# MAX_BUS.net
KiCad netlist of a schematic drawn in Altium Designer
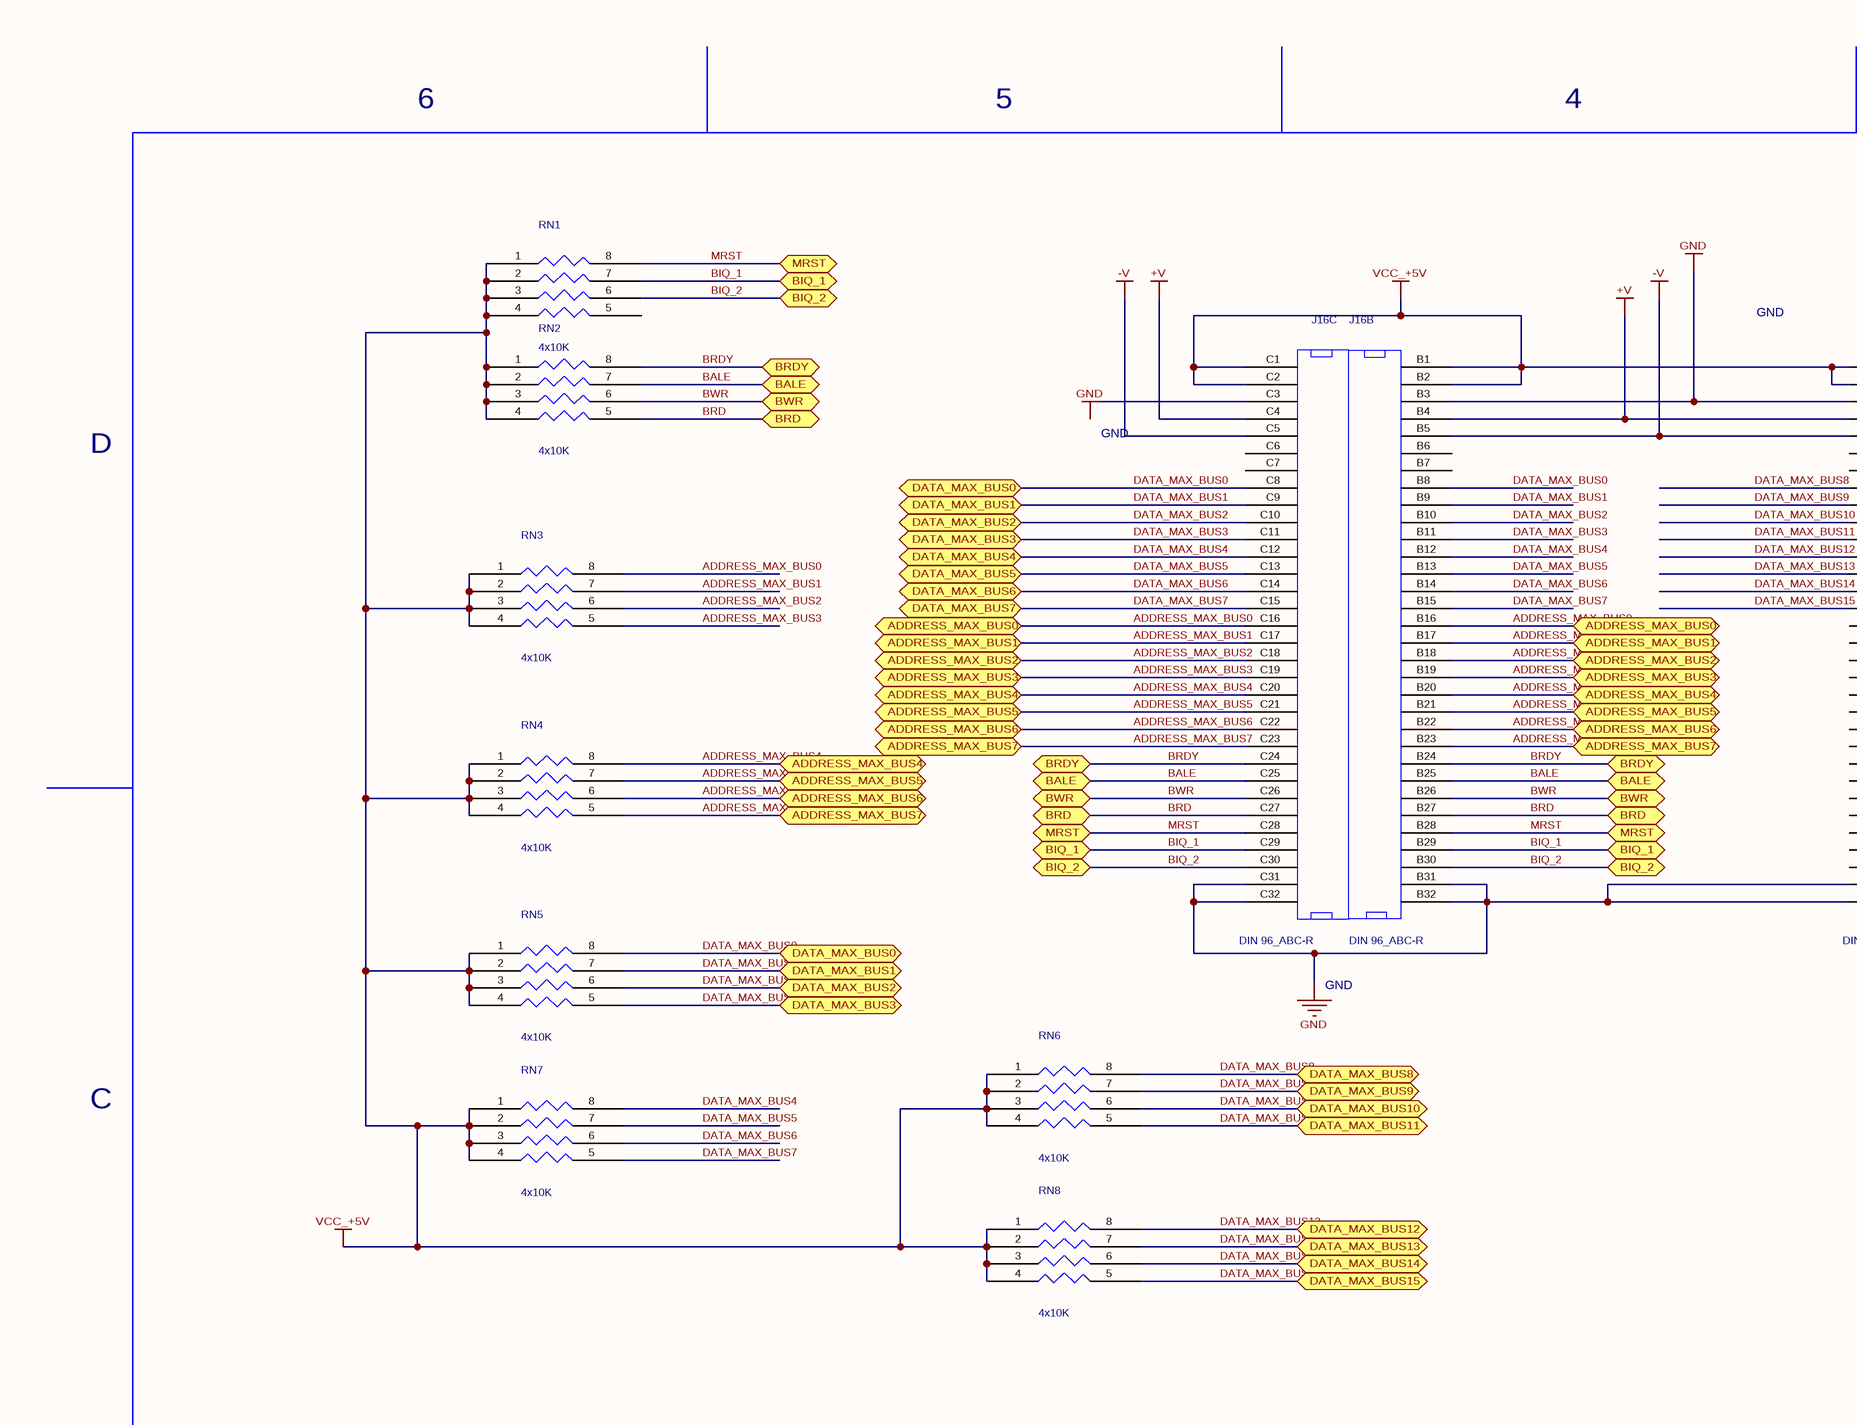
[diagram p0: MAX_BUS.SchDoc, top left]
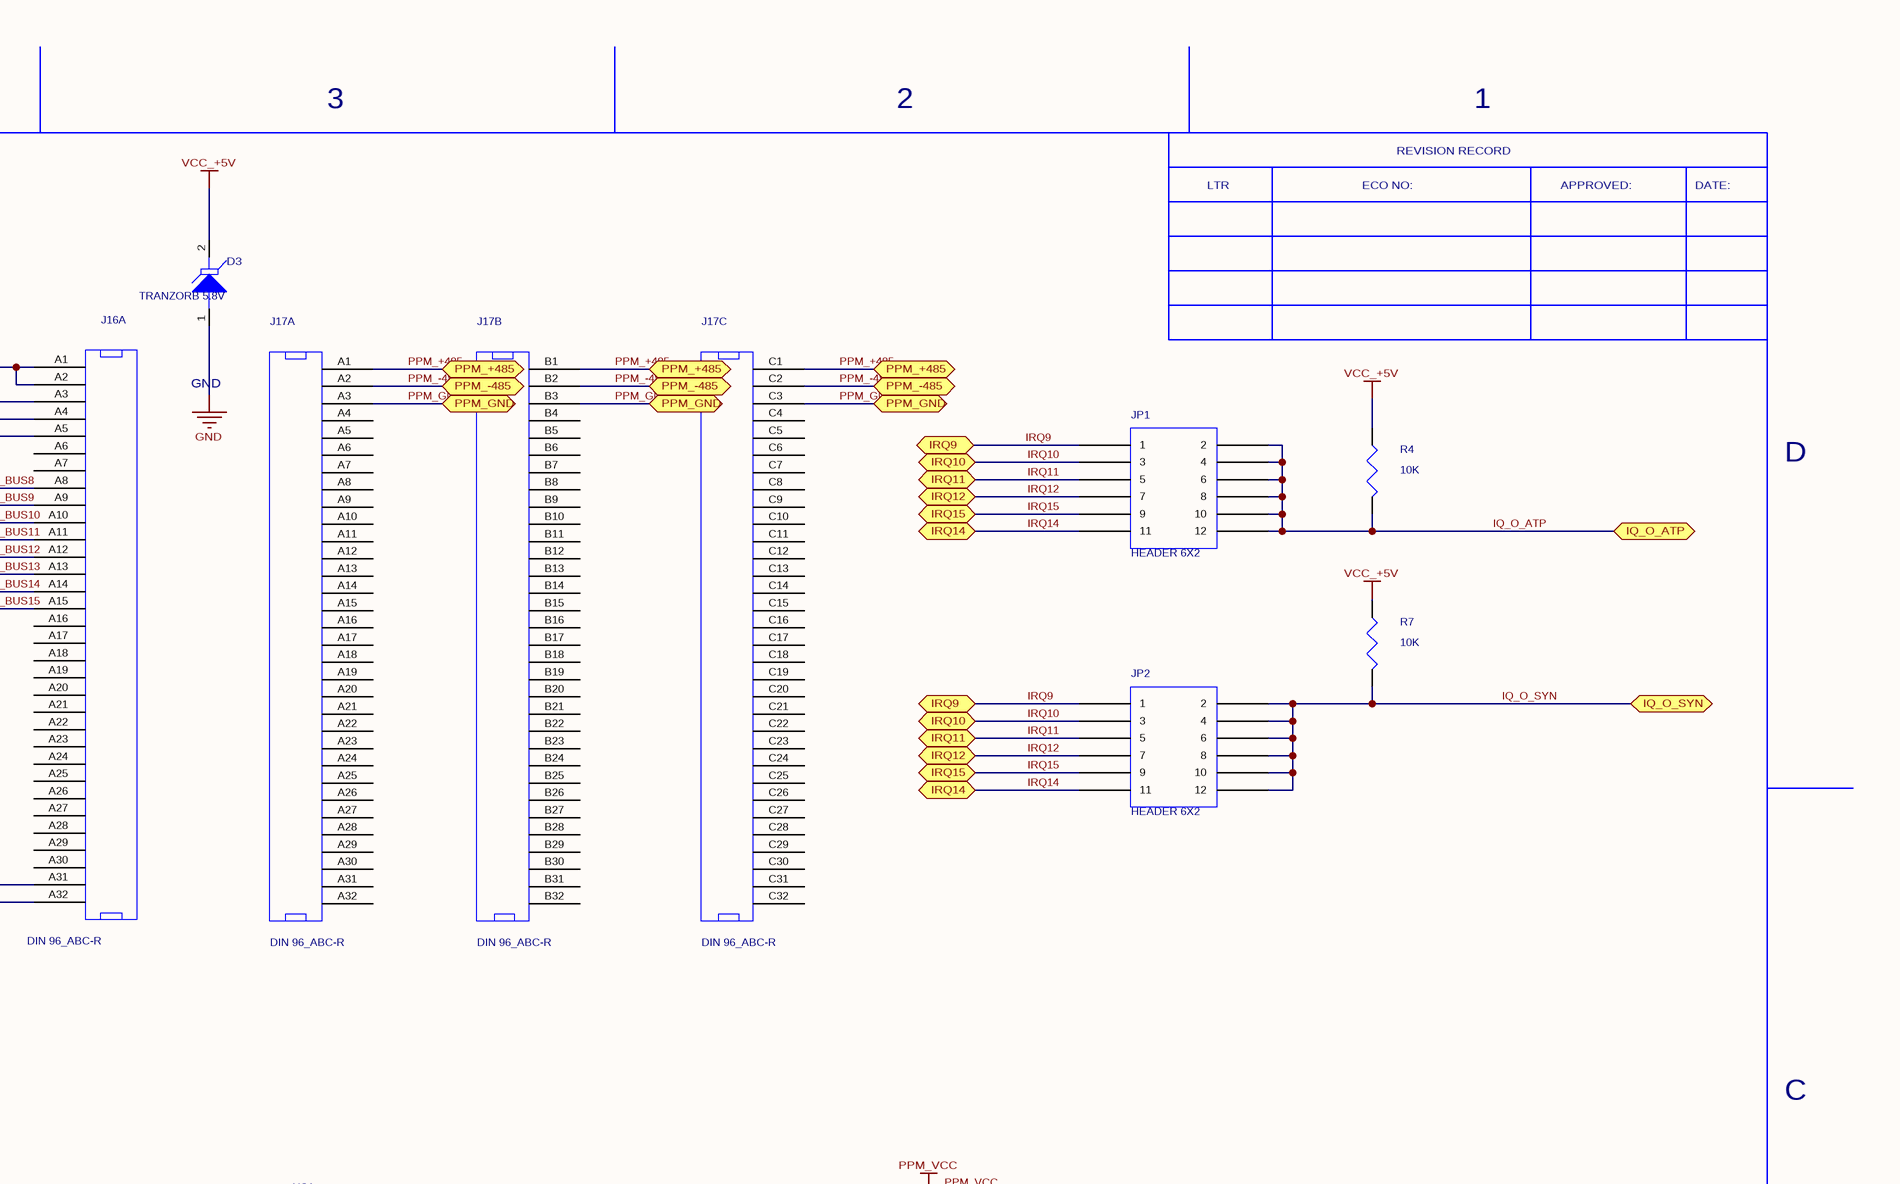
[diagram p1: MAX_BUS.SchDoc, top right]
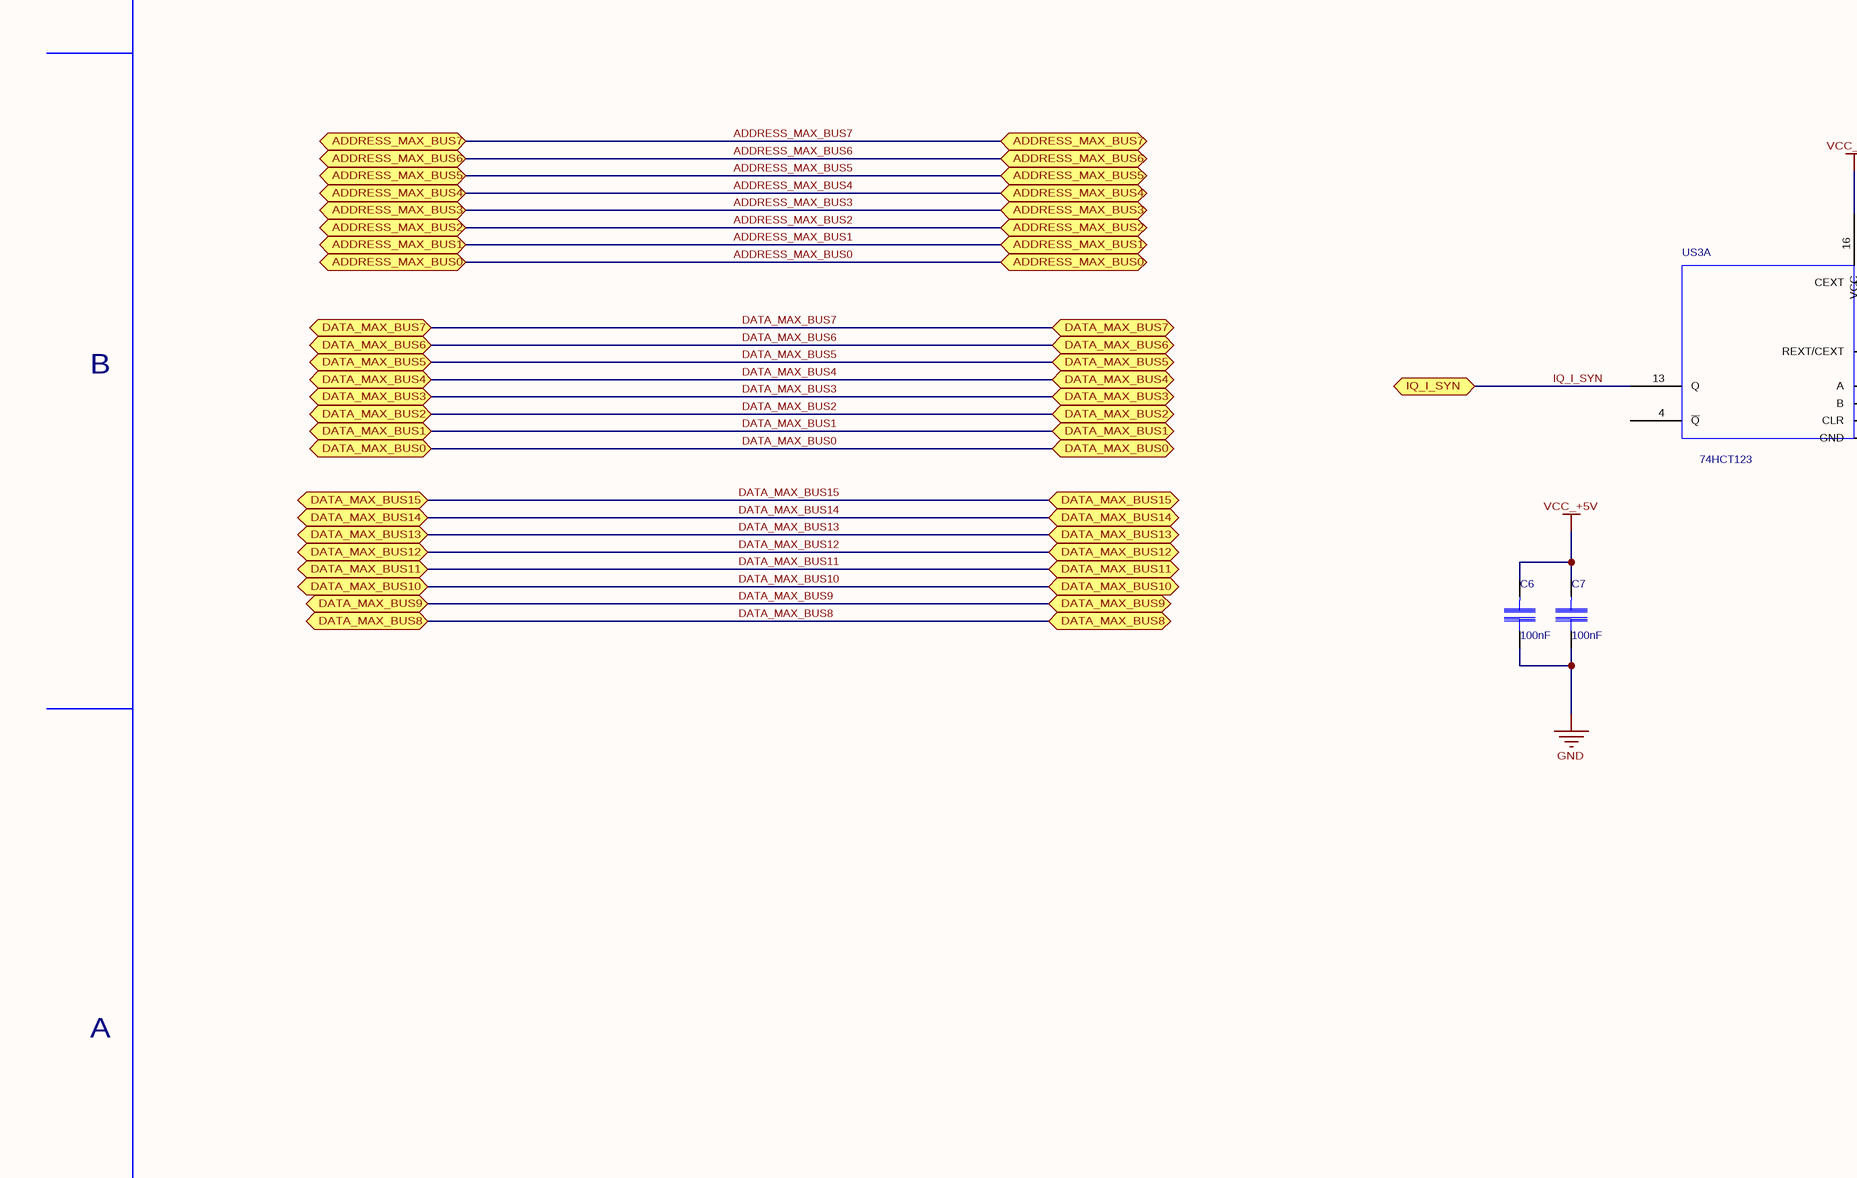
[diagram p2: MAX_BUS.SchDoc, bottom left]
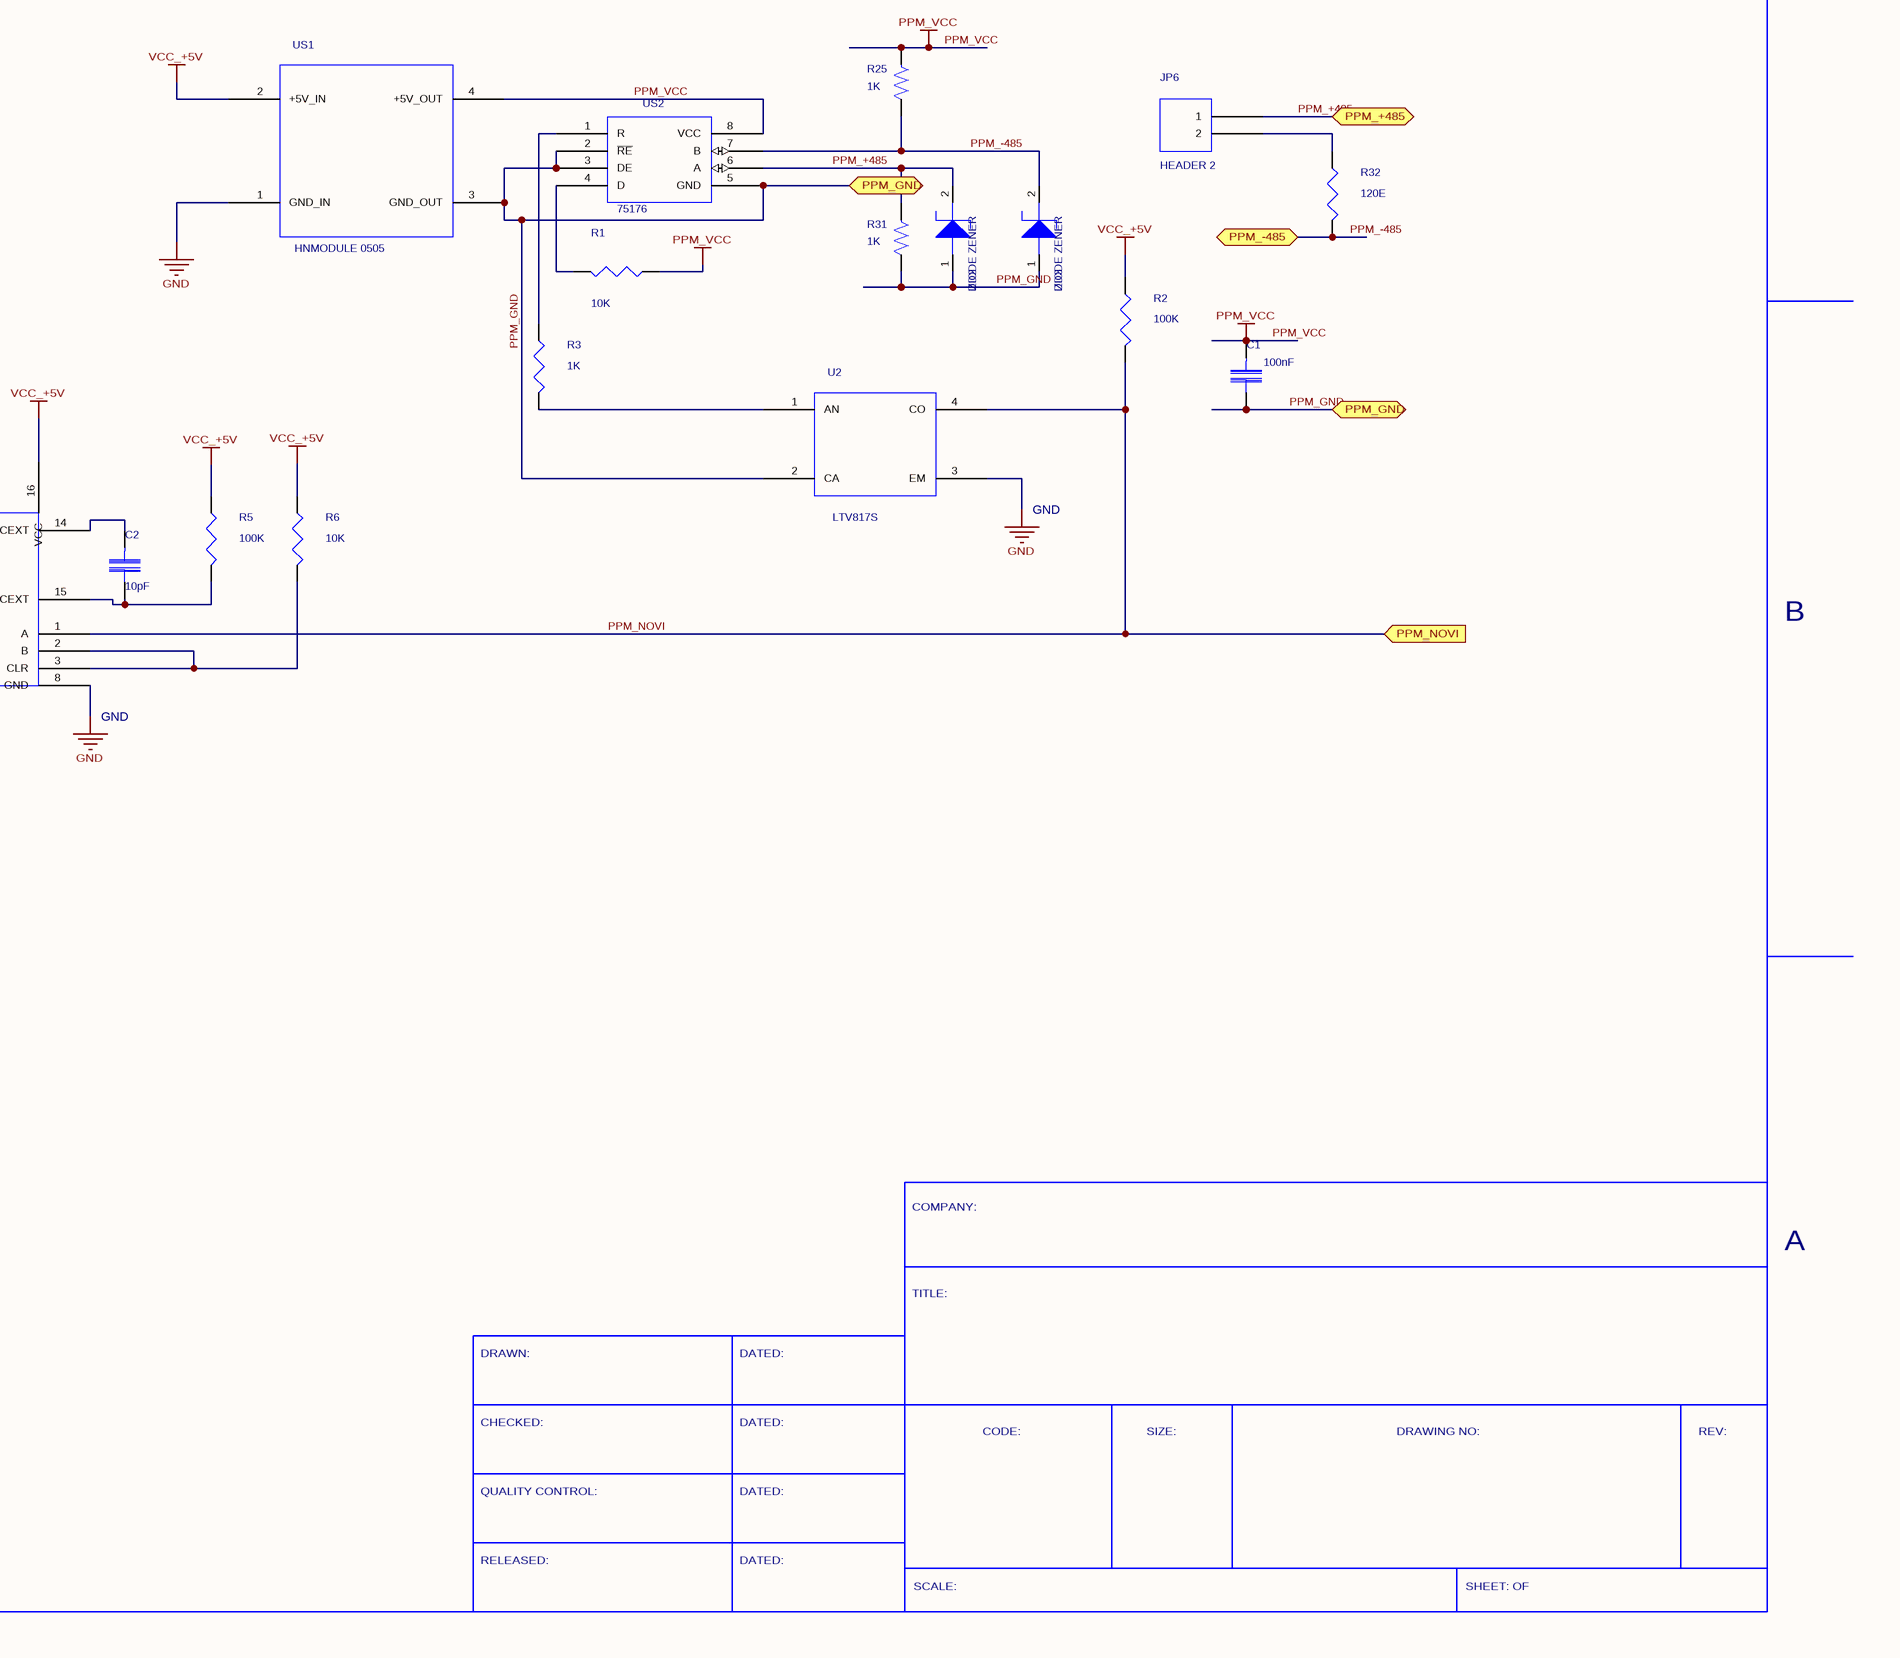
[diagram p3: MAX_BUS.SchDoc, bottom right]

(export (version "E")
  (design (tool "Eeschema 10.0.6"))
  (components
    (comp (ref "C1")
      (value "100nF")
      (footprint "SM/C_0805")
      (fields (field (name "Comment") "C"))
      (libsource (lib "*") (part "C"))
    )
    (comp (ref "C2")
      (value "10pF")
      (footprint "SM/C_0805")
      (fields (field (name "Comment") "C"))
      (libsource (lib "*") (part "C"))
    )
    (comp (ref "C6")
      (value "100nF")
      (footprint "SM/C_0805")
      (fields (field (name "Comment") "C"))
      (libsource (lib "*") (part "C"))
    )
    (comp (ref "C7")
      (value "100nF")
      (footprint "SM/C_0805")
      (fields (field (name "Comment") "C"))
      (libsource (lib "*") (part "C"))
    )
    (comp (ref "D3")
      (value "TRANZORB 5.8V")
      (footprint "SM/DO214AC_21")
      (fields (field (name "Comment") "TRANZORB_0"))
      (libsource (lib "*") (part "TRANZORB_0"))
    )
    (comp (ref "J16")
      (value "DIN 96_ABC-R")
      (footprint "DIN96_ABC/R")
      (fields (field (name "Comment") "DIN_96_ABC-R"))
      (libsource (lib "*") (part "DIN_96_ABC-R"))
    )
    (comp (ref "J17")
      (value "DIN 96_ABC-R")
      (footprint "DIN96_ABC/R")
      (fields (field (name "Comment") "DIN_96_ABC-R"))
      (libsource (lib "*") (part "DIN_96_ABC-R"))
    )
    (comp (ref "JP1")
      (value "HEADER 6X2")
      (footprint "BLKCON.100/VH/TM2OE/W.200/12")
      (fields (field (name "Comment") "HEADER_6X2"))
      (libsource (lib "*") (part "HEADER_6X2"))
    )
    (comp (ref "JP2")
      (value "HEADER 6X2")
      (footprint "BLKCON.100/VH/TM2OE/W.200/12")
      (fields (field (name "Comment") "HEADER_6X2"))
      (libsource (lib "*") (part "HEADER_6X2"))
    )
    (comp (ref "JP6")
      (value "HEADER 2")
      (footprint "JUMPER_100")
      (fields (field (name "Comment") "HEADER_2"))
      (libsource (lib "*") (part "HEADER_2"))
    )
    (comp (ref "R1")
      (value "10K")
      (footprint "SM/R_1206")
      (fields (field (name "Comment") "RESISTOR_2"))
      (libsource (lib "*") (part "RESISTOR_2"))
    )
    (comp (ref "R2")
      (value "100K")
      (footprint "SM/R_1206")
      (fields (field (name "Comment") "RESISTOR_2"))
      (libsource (lib "*") (part "RESISTOR_2"))
    )
    (comp (ref "R3")
      (value "1K")
      (footprint "SM/R_1206")
      (fields (field (name "Comment") "RESISTOR_2"))
      (libsource (lib "*") (part "RESISTOR_2"))
    )
    (comp (ref "R4")
      (value "10K")
      (footprint "SM/R_1206")
      (fields (field (name "Comment") "RESISTOR_2"))
      (libsource (lib "*") (part "RESISTOR_2"))
    )
    (comp (ref "R5")
      (value "100K")
      (footprint "SM/R_1206")
      (fields (field (name "Comment") "RESISTOR_2"))
      (libsource (lib "*") (part "RESISTOR_2"))
    )
    (comp (ref "R6")
      (value "10K")
      (footprint "SM/R_1206")
      (fields (field (name "Comment") "RESISTOR_2"))
      (libsource (lib "*") (part "RESISTOR_2"))
    )
    (comp (ref "R7")
      (value "10K")
      (footprint "SM/R_1206")
      (fields (field (name "Comment") "RESISTOR_2"))
      (libsource (lib "*") (part "RESISTOR_2"))
    )
    (comp (ref "R25")
      (value "1K")
      (footprint "SM/R_1206")
      (fields (field (name "VOLTAGE") "RVMAX") (field (name "POWER") "RMAX") (field (name "Comment") "R"))
      (libsource (lib "*") (part "R"))
    )
    (comp (ref "R31")
      (value "1K")
      (footprint "SM/R_1206")
      (fields (field (name "VOLTAGE") "RVMAX") (field (name "POWER") "RMAX") (field (name "Comment") "R"))
      (libsource (lib "*") (part "R"))
    )
    (comp (ref "R32")
      (value "120E")
      (footprint "SM/R_1206")
      (fields (field (name "Comment") "RESISTOR_2"))
      (libsource (lib "*") (part "RESISTOR_2"))
    )
    (comp (ref "RN1")
      (value "4x10K")
      (footprint "SMD_RX4")
      (fields (field (name "Comment") "RESAR_IS_4/SM"))
      (libsource (lib "*") (part "RESAR_IS_4/SM"))
    )
    (comp (ref "RN2")
      (value "4x10K")
      (footprint "SMD_RX4")
      (fields (field (name "Comment") "RESAR_IS_4/SM"))
      (libsource (lib "*") (part "RESAR_IS_4/SM"))
    )
    (comp (ref "RN3")
      (value "4x10K")
      (footprint "SMD_RX4")
      (fields (field (name "Comment") "RESAR_IS_4/SM"))
      (libsource (lib "*") (part "RESAR_IS_4/SM"))
    )
    (comp (ref "RN4")
      (value "4x10K")
      (footprint "SMD_RX4")
      (fields (field (name "Comment") "RESAR_IS_4/SM"))
      (libsource (lib "*") (part "RESAR_IS_4/SM"))
    )
    (comp (ref "RN5")
      (value "4x10K")
      (footprint "SMD_RX4")
      (fields (field (name "Comment") "RESAR_IS_4/SM"))
      (libsource (lib "*") (part "RESAR_IS_4/SM"))
    )
    (comp (ref "RN6")
      (value "4x10K")
      (footprint "SMD_RX4")
      (fields (field (name "Comment") "RESAR_IS_4/SM"))
      (libsource (lib "*") (part "RESAR_IS_4/SM"))
    )
    (comp (ref "RN7")
      (value "4x10K")
      (footprint "SMD_RX4")
      (fields (field (name "Comment") "RESAR_IS_4/SM"))
      (libsource (lib "*") (part "RESAR_IS_4/SM"))
    )
    (comp (ref "RN8")
      (value "4x10K")
      (footprint "SMD_RX4")
      (fields (field (name "Comment") "RESAR_IS_4/SM"))
      (libsource (lib "*") (part "RESAR_IS_4/SM"))
    )
    (comp (ref "U2")
      (value "LTV817S")
      (footprint "LTV814S")
      (fields (field (name "Comment") "LTV-817_0"))
      (libsource (lib "*") (part "LTV-817_0"))
    )
    (comp (ref "US1")
      (value "HNMODULE 0505")
      (footprint "DCDC55")
      (fields (field (name "Comment") "HNMODUL0505"))
      (libsource (lib "*") (part "HNMODUL0505"))
    )
    (comp (ref "US2")
      (value "75176")
      (footprint "SOG.050/8/WG.244/L.225")
      (libsource (lib "*") (part "75176"))
    )
    (comp (ref "US3")
      (value "74HCT123")
      (footprint "SOG.050/16/WG.244/L.375")
      (fields (field (name "Comment") "74HC123_0"))
      (libsource (lib "*") (part "74HC123_0"))
    )
    (comp (ref "ZD2")
      (value "DIODE ZENER")
      (footprint "SM/D_1206_21")
      (fields (field (name "Comment") "DIODE_ZENER_0"))
      (libsource (lib "*") (part "DIODE_ZENER_0"))
    )
    (comp (ref "ZD3")
      (value "DIODE ZENER")
      (footprint "SM/D_1206_21")
      (fields (field (name "Comment") "DIODE_ZENER_0"))
      (libsource (lib "*") (part "DIODE_ZENER_0"))
    )
  )
  (nets
    (net (code "1") (name "+V") (class "Default")
      (node (ref "J16") (pin "A4") (pinfunction "A4_A4") (pintype "passive"))
      (node (ref "J16") (pin "B4") (pinfunction "B4_B4") (pintype "passive"))
      (node (ref "J16") (pin "C4") (pinfunction "C4_C4") (pintype "passive"))
    )
    (net (code "2") (name "-V") (class "Default")
      (node (ref "J16") (pin "A5") (pinfunction "A5_A5") (pintype "passive"))
      (node (ref "J16") (pin "B5") (pinfunction "B5_B5") (pintype "passive"))
      (node (ref "J16") (pin "C5") (pinfunction "C5_C5") (pintype "passive"))
    )
    (net (code "3") (name "/ADDRESS_MAX_BUS0") (class "Default")
      (node (ref "J16") (pin "B16") (pinfunction "B16_B16") (pintype "passive"))
      (node (ref "J16") (pin "C16") (pinfunction "C16_C16") (pintype "passive"))
      (node (ref "RN3") (pin "8") (pinfunction "8_8") (pintype "passive"))
    )
    (net (code "4") (name "/ADDRESS_MAX_BUS1") (class "Default")
      (node (ref "J16") (pin "B17") (pinfunction "B17_B17") (pintype "passive"))
      (node (ref "J16") (pin "C17") (pinfunction "C17_C17") (pintype "passive"))
      (node (ref "RN3") (pin "7") (pinfunction "7_7") (pintype "passive"))
    )
    (net (code "5") (name "/ADDRESS_MAX_BUS2") (class "Default")
      (node (ref "J16") (pin "B18") (pinfunction "B18_B18") (pintype "passive"))
      (node (ref "J16") (pin "C18") (pinfunction "C18_C18") (pintype "passive"))
      (node (ref "RN3") (pin "6") (pinfunction "6_6") (pintype "passive"))
    )
    (net (code "6") (name "/ADDRESS_MAX_BUS3") (class "Default")
      (node (ref "J16") (pin "B19") (pinfunction "B19_B19") (pintype "passive"))
      (node (ref "J16") (pin "C19") (pinfunction "C19_C19") (pintype "passive"))
      (node (ref "RN3") (pin "5") (pinfunction "5_5") (pintype "passive"))
    )
    (net (code "7") (name "/ADDRESS_MAX_BUS4") (class "Default")
      (node (ref "J16") (pin "B20") (pinfunction "B20_B20") (pintype "passive"))
      (node (ref "J16") (pin "C20") (pinfunction "C20_C20") (pintype "passive"))
      (node (ref "RN4") (pin "8") (pinfunction "8_8") (pintype "passive"))
    )
    (net (code "8") (name "/ADDRESS_MAX_BUS5") (class "Default")
      (node (ref "J16") (pin "B21") (pinfunction "B21_B21") (pintype "passive"))
      (node (ref "J16") (pin "C21") (pinfunction "C21_C21") (pintype "passive"))
      (node (ref "RN4") (pin "7") (pinfunction "7_7") (pintype "passive"))
    )
    (net (code "9") (name "/ADDRESS_MAX_BUS6") (class "Default")
      (node (ref "J16") (pin "B22") (pinfunction "B22_B22") (pintype "passive"))
      (node (ref "J16") (pin "C22") (pinfunction "C22_C22") (pintype "passive"))
      (node (ref "RN4") (pin "6") (pinfunction "6_6") (pintype "passive"))
    )
    (net (code "10") (name "/ADDRESS_MAX_BUS7") (class "Default")
      (node (ref "J16") (pin "B23") (pinfunction "B23_B23") (pintype "passive"))
      (node (ref "J16") (pin "C23") (pinfunction "C23_C23") (pintype "passive"))
      (node (ref "RN4") (pin "5") (pinfunction "5_5") (pintype "passive"))
    )
    (net (code "11") (name "/BALE") (class "Default")
      (node (ref "J16") (pin "B25") (pinfunction "B25_B25") (pintype "passive"))
      (node (ref "J16") (pin "C25") (pinfunction "C25_C25") (pintype "passive"))
      (node (ref "RN2") (pin "7") (pinfunction "7_7") (pintype "passive"))
    )
    (net (code "12") (name "/BIQ_1") (class "Default")
      (node (ref "J16") (pin "B29") (pinfunction "B29_B29") (pintype "passive"))
      (node (ref "J16") (pin "C29") (pinfunction "C29_C29") (pintype "passive"))
      (node (ref "RN1") (pin "7") (pinfunction "7_7") (pintype "passive"))
    )
    (net (code "13") (name "/BIQ_2") (class "Default")
      (node (ref "J16") (pin "B30") (pinfunction "B30_B30") (pintype "passive"))
      (node (ref "J16") (pin "C30") (pinfunction "C30_C30") (pintype "passive"))
      (node (ref "RN1") (pin "6") (pinfunction "6_6") (pintype "passive"))
    )
    (net (code "14") (name "/BRD") (class "Default")
      (node (ref "J16") (pin "B27") (pinfunction "B27_B27") (pintype "passive"))
      (node (ref "J16") (pin "C27") (pinfunction "C27_C27") (pintype "passive"))
      (node (ref "RN2") (pin "5") (pinfunction "5_5") (pintype "passive"))
    )
    (net (code "15") (name "/BRDY") (class "Default")
      (node (ref "J16") (pin "B24") (pinfunction "B24_B24") (pintype "passive"))
      (node (ref "J16") (pin "C24") (pinfunction "C24_C24") (pintype "passive"))
      (node (ref "RN2") (pin "8") (pinfunction "8_8") (pintype "passive"))
    )
    (net (code "16") (name "/BWR") (class "Default")
      (node (ref "J16") (pin "B26") (pinfunction "B26_B26") (pintype "passive"))
      (node (ref "J16") (pin "C26") (pinfunction "C26_C26") (pintype "passive"))
      (node (ref "RN2") (pin "6") (pinfunction "6_6") (pintype "passive"))
    )
    (net (code "17") (name "/DATA_MAX_BUS0") (class "Default")
      (node (ref "J16") (pin "B8") (pinfunction "B8_B8") (pintype "passive"))
      (node (ref "J16") (pin "C8") (pinfunction "C8_C8") (pintype "passive"))
      (node (ref "RN5") (pin "8") (pinfunction "8_8") (pintype "passive"))
    )
    (net (code "18") (name "/DATA_MAX_BUS1") (class "Default")
      (node (ref "J16") (pin "B9") (pinfunction "B9_B9") (pintype "passive"))
      (node (ref "J16") (pin "C9") (pinfunction "C9_C9") (pintype "passive"))
      (node (ref "RN5") (pin "7") (pinfunction "7_7") (pintype "passive"))
    )
    (net (code "19") (name "/DATA_MAX_BUS2") (class "Default")
      (node (ref "J16") (pin "B10") (pinfunction "B10_B10") (pintype "passive"))
      (node (ref "J16") (pin "C10") (pinfunction "C10_C10") (pintype "passive"))
      (node (ref "RN5") (pin "6") (pinfunction "6_6") (pintype "passive"))
    )
    (net (code "20") (name "/DATA_MAX_BUS3") (class "Default")
      (node (ref "J16") (pin "B11") (pinfunction "B11_B11") (pintype "passive"))
      (node (ref "J16") (pin "C11") (pinfunction "C11_C11") (pintype "passive"))
      (node (ref "RN5") (pin "5") (pinfunction "5_5") (pintype "passive"))
    )
    (net (code "21") (name "/DATA_MAX_BUS4") (class "Default")
      (node (ref "J16") (pin "B12") (pinfunction "B12_B12") (pintype "passive"))
      (node (ref "J16") (pin "C12") (pinfunction "C12_C12") (pintype "passive"))
      (node (ref "RN7") (pin "8") (pinfunction "8_8") (pintype "passive"))
    )
    (net (code "22") (name "/DATA_MAX_BUS5") (class "Default")
      (node (ref "J16") (pin "B13") (pinfunction "B13_B13") (pintype "passive"))
      (node (ref "J16") (pin "C13") (pinfunction "C13_C13") (pintype "passive"))
      (node (ref "RN7") (pin "7") (pinfunction "7_7") (pintype "passive"))
    )
    (net (code "23") (name "/DATA_MAX_BUS6") (class "Default")
      (node (ref "J16") (pin "B14") (pinfunction "B14_B14") (pintype "passive"))
      (node (ref "J16") (pin "C14") (pinfunction "C14_C14") (pintype "passive"))
      (node (ref "RN7") (pin "6") (pinfunction "6_6") (pintype "passive"))
    )
    (net (code "24") (name "/DATA_MAX_BUS7") (class "Default")
      (node (ref "J16") (pin "B15") (pinfunction "B15_B15") (pintype "passive"))
      (node (ref "J16") (pin "C15") (pinfunction "C15_C15") (pintype "passive"))
      (node (ref "RN7") (pin "5") (pinfunction "5_5") (pintype "passive"))
    )
    (net (code "25") (name "/DATA_MAX_BUS8") (class "Default")
      (node (ref "J16") (pin "A8") (pinfunction "A8_A8") (pintype "passive"))
      (node (ref "RN6") (pin "8") (pinfunction "8_8") (pintype "passive"))
    )
    (net (code "26") (name "/DATA_MAX_BUS9") (class "Default")
      (node (ref "J16") (pin "A9") (pinfunction "A9_A9") (pintype "passive"))
      (node (ref "RN6") (pin "7") (pinfunction "7_7") (pintype "passive"))
    )
    (net (code "27") (name "/DATA_MAX_BUS10") (class "Default")
      (node (ref "J16") (pin "A10") (pinfunction "A10_A10") (pintype "passive"))
      (node (ref "RN6") (pin "6") (pinfunction "6_6") (pintype "passive"))
    )
    (net (code "28") (name "/DATA_MAX_BUS11") (class "Default")
      (node (ref "J16") (pin "A11") (pinfunction "A11_A11") (pintype "passive"))
      (node (ref "RN6") (pin "5") (pinfunction "5_5") (pintype "passive"))
    )
    (net (code "29") (name "/DATA_MAX_BUS12") (class "Default")
      (node (ref "J16") (pin "A12") (pinfunction "A12_A12") (pintype "passive"))
      (node (ref "RN8") (pin "8") (pinfunction "8_8") (pintype "passive"))
    )
    (net (code "30") (name "/DATA_MAX_BUS13") (class "Default")
      (node (ref "J16") (pin "A13") (pinfunction "A13_A13") (pintype "passive"))
      (node (ref "RN8") (pin "7") (pinfunction "7_7") (pintype "passive"))
    )
    (net (code "31") (name "/DATA_MAX_BUS14") (class "Default")
      (node (ref "J16") (pin "A14") (pinfunction "A14_A14") (pintype "passive"))
      (node (ref "RN8") (pin "6") (pinfunction "6_6") (pintype "passive"))
    )
    (net (code "32") (name "/DATA_MAX_BUS15") (class "Default")
      (node (ref "J16") (pin "A15") (pinfunction "A15_A15") (pintype "passive"))
      (node (ref "RN8") (pin "5") (pinfunction "5_5") (pintype "passive"))
    )
    (net (code "33") (name "/IQ_I_SYN") (class "Default")
      (node (ref "US3") (pin "13") (pinfunction "Q_13") (pintype "passive"))
    )
    (net (code "34") (name "/IQ_O_ATP") (class "Default")
      (node (ref "JP1") (pin "10") (pinfunction "10_10") (pintype "passive"))
      (node (ref "JP1") (pin "12") (pinfunction "12_12") (pintype "passive"))
      (node (ref "JP1") (pin "2") (pinfunction "2_2") (pintype "passive"))
      (node (ref "JP1") (pin "4") (pinfunction "4_4") (pintype "passive"))
      (node (ref "JP1") (pin "6") (pinfunction "6_6") (pintype "passive"))
      (node (ref "JP1") (pin "8") (pinfunction "8_8") (pintype "passive"))
      (node (ref "R4") (pin "2") (pinfunction "2_2") (pintype "passive"))
    )
    (net (code "35") (name "/IQ_O_SYN") (class "Default")
      (node (ref "JP2") (pin "10") (pinfunction "10_10") (pintype "passive"))
      (node (ref "JP2") (pin "12") (pinfunction "12_12") (pintype "passive"))
      (node (ref "JP2") (pin "2") (pinfunction "2_2") (pintype "passive"))
      (node (ref "JP2") (pin "4") (pinfunction "4_4") (pintype "passive"))
      (node (ref "JP2") (pin "6") (pinfunction "6_6") (pintype "passive"))
      (node (ref "JP2") (pin "8") (pinfunction "8_8") (pintype "passive"))
      (node (ref "R7") (pin "2") (pinfunction "2_2") (pintype "passive"))
    )
    (net (code "36") (name "/IRQ9") (class "Default")
      (node (ref "JP1") (pin "1") (pinfunction "1_1") (pintype "passive"))
      (node (ref "JP2") (pin "1") (pinfunction "1_1") (pintype "passive"))
    )
    (net (code "37") (name "/IRQ10") (class "Default")
      (node (ref "JP1") (pin "3") (pinfunction "3_3") (pintype "passive"))
      (node (ref "JP2") (pin "3") (pinfunction "3_3") (pintype "passive"))
    )
    (net (code "38") (name "/IRQ11") (class "Default")
      (node (ref "JP1") (pin "5") (pinfunction "5_5") (pintype "passive"))
      (node (ref "JP2") (pin "5") (pinfunction "5_5") (pintype "passive"))
    )
    (net (code "39") (name "/IRQ12") (class "Default")
      (node (ref "JP1") (pin "7") (pinfunction "7_7") (pintype "passive"))
      (node (ref "JP2") (pin "7") (pinfunction "7_7") (pintype "passive"))
    )
    (net (code "40") (name "/IRQ14") (class "Default")
      (node (ref "JP1") (pin "11") (pinfunction "11_11") (pintype "passive"))
      (node (ref "JP2") (pin "11") (pinfunction "11_11") (pintype "passive"))
    )
    (net (code "41") (name "/IRQ15") (class "Default")
      (node (ref "JP1") (pin "9") (pinfunction "9_9") (pintype "passive"))
      (node (ref "JP2") (pin "9") (pinfunction "9_9") (pintype "passive"))
    )
    (net (code "42") (name "/MRST") (class "Default")
      (node (ref "J16") (pin "B28") (pinfunction "B28_B28") (pintype "passive"))
      (node (ref "J16") (pin "C28") (pinfunction "C28_C28") (pintype "passive"))
      (node (ref "RN1") (pin "8") (pinfunction "8_8") (pintype "passive"))
    )
    (net (code "43") (name "/PPM_+485") (class "Default")
      (node (ref "J17") (pin "A1") (pinfunction "A1_A1") (pintype "passive"))
      (node (ref "J17") (pin "B1") (pinfunction "B1_B1") (pintype "passive"))
      (node (ref "J17") (pin "C1") (pinfunction "C1_C1") (pintype "passive"))
      (node (ref "JP6") (pin "1") (pinfunction "1_1") (pintype "passive"))
      (node (ref "R31") (pin "1") (pinfunction "1_1") (pintype "passive"))
      (node (ref "US2") (pin "6") (pinfunction "A_6") (pintype "bidirectional"))
      (node (ref "ZD2") (pin "2") (pinfunction "CATHODE_2") (pintype "passive"))
    )
    (net (code "44") (name "/PPM_-485") (class "Default")
      (node (ref "J17") (pin "A2") (pinfunction "A2_A2") (pintype "passive"))
      (node (ref "J17") (pin "B2") (pinfunction "B2_B2") (pintype "passive"))
      (node (ref "J17") (pin "C2") (pinfunction "C2_C2") (pintype "passive"))
      (node (ref "R25") (pin "2") (pinfunction "2_2") (pintype "passive"))
      (node (ref "R32") (pin "2") (pinfunction "2_2") (pintype "passive"))
      (node (ref "US2") (pin "7") (pinfunction "B_7") (pintype "bidirectional"))
      (node (ref "ZD3") (pin "2") (pinfunction "CATHODE_2") (pintype "passive"))
    )
    (net (code "45") (name "/PPM_GND") (class "Default")
      (node (ref "C1") (pin "2") (pinfunction "2_2") (pintype "passive"))
      (node (ref "J17") (pin "A3") (pinfunction "A3_A3") (pintype "passive"))
      (node (ref "J17") (pin "B3") (pinfunction "B3_B3") (pintype "passive"))
      (node (ref "J17") (pin "C3") (pinfunction "C3_C3") (pintype "passive"))
      (node (ref "R31") (pin "2") (pinfunction "2_2") (pintype "passive"))
      (node (ref "U2") (pin "2") (pinfunction "CA_2") (pintype "passive"))
      (node (ref "US1") (pin "3") (pinfunction "GND_OUT_3") (pintype "passive"))
      (node (ref "US2") (pin "2") (pinfunction "RE_2") (pintype "passive"))
      (node (ref "US2") (pin "3") (pinfunction "DE_3") (pintype "passive"))
      (node (ref "US2") (pin "5") (pinfunction "GND_5") (pintype "passive"))
      (node (ref "ZD2") (pin "1") (pinfunction "ANODE_1") (pintype "passive"))
      (node (ref "ZD3") (pin "1") (pinfunction "ANODE_1") (pintype "passive"))
    )
    (net (code "46") (name "/PPM_NOVI") (class "Default")
      (node (ref "R2") (pin "2") (pinfunction "2_2") (pintype "passive"))
      (node (ref "U2") (pin "4") (pinfunction "CO_4") (pintype "passive"))
      (node (ref "US3") (pin "1") (pinfunction "A_1") (pintype "passive"))
    )
    (net (code "47") (name "GND") (class "Default")
      (node (ref "C6") (pin "2") (pinfunction "2_2") (pintype "passive"))
      (node (ref "C7") (pin "2") (pinfunction "2_2") (pintype "passive"))
      (node (ref "D3") (pin "1") (pinfunction "ANODE_1") (pintype "passive"))
      (node (ref "J16") (pin "A3") (pinfunction "A3_A3") (pintype "passive"))
      (node (ref "J16") (pin "A31") (pinfunction "A31_A31") (pintype "passive"))
      (node (ref "J16") (pin "A32") (pinfunction "A32_A32") (pintype "passive"))
      (node (ref "J16") (pin "B3") (pinfunction "B3_B3") (pintype "passive"))
      (node (ref "J16") (pin "B31") (pinfunction "B31_B31") (pintype "passive"))
      (node (ref "J16") (pin "B32") (pinfunction "B32_B32") (pintype "passive"))
      (node (ref "J16") (pin "C3") (pinfunction "C3_C3") (pintype "passive"))
      (node (ref "J16") (pin "C31") (pinfunction "C31_C31") (pintype "passive"))
      (node (ref "J16") (pin "C32") (pinfunction "C32_C32") (pintype "passive"))
      (node (ref "U2") (pin "3") (pinfunction "EM_3") (pintype "passive"))
      (node (ref "US1") (pin "1") (pinfunction "GND_IN_1") (pintype "passive"))
      (node (ref "US3") (pin "8") (pinfunction "GND_8") (pintype "power_in"))
    )
    (net (code "48") (name "Net-(JP6-Pad2)") (class "Default")
      (node (ref "JP6") (pin "2") (pinfunction "2_2") (pintype "passive"))
      (node (ref "R32") (pin "1") (pinfunction "1_1") (pintype "passive"))
    )
    (net (code "49") (name "Net-(U2-AN)") (class "Default")
      (node (ref "R3") (pin "2") (pinfunction "2_2") (pintype "passive"))
      (node (ref "U2") (pin "1") (pinfunction "AN_1") (pintype "passive"))
    )
    (net (code "50") (name "Net-(US2-D)") (class "Default")
      (node (ref "R1") (pin "2") (pinfunction "2_2") (pintype "passive"))
      (node (ref "US2") (pin "4") (pinfunction "D_4") (pintype "passive"))
    )
    (net (code "51") (name "Net-(US2-R)") (class "Default")
      (node (ref "R3") (pin "1") (pinfunction "1_1") (pintype "passive"))
      (node (ref "US2") (pin "1") (pinfunction "R_1") (pintype "tri_state"))
    )
    (net (code "52") (name "Net-(US3A-B)") (class "Default")
      (node (ref "R6") (pin "2") (pinfunction "2_2") (pintype "passive"))
      (node (ref "US3") (pin "2") (pinfunction "B_2") (pintype "passive"))
      (node (ref "US3") (pin "3") (pinfunction "CLR_3") (pintype "passive"))
    )
    (net (code "53") (name "Net-(US3A-CEXT)") (class "Default")
      (node (ref "C2") (pin "1") (pinfunction "1_1") (pintype "passive"))
      (node (ref "US3") (pin "14") (pinfunction "CEXT_14") (pintype "passive"))
    )
    (net (code "54") (name "Net-(US3A-REXT{slash}CEXT)") (class "Default")
      (node (ref "C2") (pin "2") (pinfunction "2_2") (pintype "passive"))
      (node (ref "R5") (pin "2") (pinfunction "2_2") (pintype "passive"))
      (node (ref "US3") (pin "15") (pinfunction "REXT/CEXT_15") (pintype "passive"))
    )
    (net (code "55") (name "PPM_VCC") (class "Default")
      (node (ref "C1") (pin "1") (pinfunction "1_1") (pintype "passive"))
      (node (ref "R1") (pin "1") (pinfunction "1_1") (pintype "passive"))
      (node (ref "R25") (pin "1") (pinfunction "1_1") (pintype "passive"))
      (node (ref "US1") (pin "4") (pinfunction "+5V_OUT_4") (pintype "power_in"))
      (node (ref "US2") (pin "8") (pinfunction "VCC_8") (pintype "passive"))
    )
    (net (code "56") (name "VCC_+5V") (class "Default")
      (node (ref "C6") (pin "1") (pinfunction "1_1") (pintype "passive"))
      (node (ref "C7") (pin "1") (pinfunction "1_1") (pintype "passive"))
      (node (ref "D3") (pin "2") (pinfunction "CATHODE_2") (pintype "passive"))
      (node (ref "J16") (pin "A1") (pinfunction "A1_A1") (pintype "passive"))
      (node (ref "J16") (pin "A2") (pinfunction "A2_A2") (pintype "passive"))
      (node (ref "J16") (pin "B1") (pinfunction "B1_B1") (pintype "passive"))
      (node (ref "J16") (pin "B2") (pinfunction "B2_B2") (pintype "passive"))
      (node (ref "J16") (pin "C1") (pinfunction "C1_C1") (pintype "passive"))
      (node (ref "J16") (pin "C2") (pinfunction "C2_C2") (pintype "passive"))
      (node (ref "R2") (pin "1") (pinfunction "1_1") (pintype "passive"))
      (node (ref "R4") (pin "1") (pinfunction "1_1") (pintype "passive"))
      (node (ref "R5") (pin "1") (pinfunction "1_1") (pintype "passive"))
      (node (ref "R6") (pin "1") (pinfunction "1_1") (pintype "passive"))
      (node (ref "R7") (pin "1") (pinfunction "1_1") (pintype "passive"))
      (node (ref "RN1") (pin "1") (pinfunction "1_1") (pintype "passive"))
      (node (ref "RN1") (pin "2") (pinfunction "2_2") (pintype "passive"))
      (node (ref "RN1") (pin "3") (pinfunction "3_3") (pintype "passive"))
      (node (ref "RN1") (pin "4") (pinfunction "4_4") (pintype "passive"))
      (node (ref "RN2") (pin "1") (pinfunction "1_1") (pintype "passive"))
      (node (ref "RN2") (pin "2") (pinfunction "2_2") (pintype "passive"))
      (node (ref "RN2") (pin "3") (pinfunction "3_3") (pintype "passive"))
      (node (ref "RN2") (pin "4") (pinfunction "4_4") (pintype "passive"))
      (node (ref "RN3") (pin "1") (pinfunction "1_1") (pintype "passive"))
      (node (ref "RN3") (pin "2") (pinfunction "2_2") (pintype "passive"))
      (node (ref "RN3") (pin "3") (pinfunction "3_3") (pintype "passive"))
      (node (ref "RN3") (pin "4") (pinfunction "4_4") (pintype "passive"))
      (node (ref "RN4") (pin "1") (pinfunction "1_1") (pintype "passive"))
      (node (ref "RN4") (pin "2") (pinfunction "2_2") (pintype "passive"))
      (node (ref "RN4") (pin "3") (pinfunction "3_3") (pintype "passive"))
      (node (ref "RN4") (pin "4") (pinfunction "4_4") (pintype "passive"))
      (node (ref "RN5") (pin "1") (pinfunction "1_1") (pintype "passive"))
      (node (ref "RN5") (pin "2") (pinfunction "2_2") (pintype "passive"))
      (node (ref "RN5") (pin "3") (pinfunction "3_3") (pintype "passive"))
      (node (ref "RN5") (pin "4") (pinfunction "4_4") (pintype "passive"))
      (node (ref "RN6") (pin "1") (pinfunction "1_1") (pintype "passive"))
      (node (ref "RN6") (pin "2") (pinfunction "2_2") (pintype "passive"))
      (node (ref "RN6") (pin "3") (pinfunction "3_3") (pintype "passive"))
      (node (ref "RN6") (pin "4") (pinfunction "4_4") (pintype "passive"))
      (node (ref "RN7") (pin "1") (pinfunction "1_1") (pintype "passive"))
      (node (ref "RN7") (pin "2") (pinfunction "2_2") (pintype "passive"))
      (node (ref "RN7") (pin "3") (pinfunction "3_3") (pintype "passive"))
      (node (ref "RN7") (pin "4") (pinfunction "4_4") (pintype "passive"))
      (node (ref "RN8") (pin "1") (pinfunction "1_1") (pintype "passive"))
      (node (ref "RN8") (pin "2") (pinfunction "2_2") (pintype "passive"))
      (node (ref "RN8") (pin "3") (pinfunction "3_3") (pintype "passive"))
      (node (ref "RN8") (pin "4") (pinfunction "4_4") (pintype "passive"))
      (node (ref "US1") (pin "2") (pinfunction "+5V_IN_2") (pintype "power_in"))
      (node (ref "US3") (pin "16") (pinfunction "VCC_16") (pintype "power_in"))
    )
    (net (code "57") (name "unconnected-(J16-PadA6)") (class "Default")
      (node (ref "J16") (pin "A6") (pinfunction "A6_A6") (pintype "passive"))
    )
    (net (code "58") (name "unconnected-(J16-PadA7)") (class "Default")
      (node (ref "J16") (pin "A7") (pinfunction "A7_A7") (pintype "passive"))
    )
    (net (code "59") (name "unconnected-(J16-PadA16)") (class "Default")
      (node (ref "J16") (pin "A16") (pinfunction "A16_A16") (pintype "passive"))
    )
    (net (code "60") (name "unconnected-(J16-PadA17)") (class "Default")
      (node (ref "J16") (pin "A17") (pinfunction "A17_A17") (pintype "passive"))
    )
    (net (code "61") (name "unconnected-(J16-PadA18)") (class "Default")
      (node (ref "J16") (pin "A18") (pinfunction "A18_A18") (pintype "passive"))
    )
    (net (code "62") (name "unconnected-(J16-PadA19)") (class "Default")
      (node (ref "J16") (pin "A19") (pinfunction "A19_A19") (pintype "passive"))
    )
    (net (code "63") (name "unconnected-(J16-PadA20)") (class "Default")
      (node (ref "J16") (pin "A20") (pinfunction "A20_A20") (pintype "passive"))
    )
    (net (code "64") (name "unconnected-(J16-PadA21)") (class "Default")
      (node (ref "J16") (pin "A21") (pinfunction "A21_A21") (pintype "passive"))
    )
    (net (code "65") (name "unconnected-(J16-PadA22)") (class "Default")
      (node (ref "J16") (pin "A22") (pinfunction "A22_A22") (pintype "passive"))
    )
    (net (code "66") (name "unconnected-(J16-PadA23)") (class "Default")
      (node (ref "J16") (pin "A23") (pinfunction "A23_A23") (pintype "passive"))
    )
    (net (code "67") (name "unconnected-(J16-PadA24)") (class "Default")
      (node (ref "J16") (pin "A24") (pinfunction "A24_A24") (pintype "passive"))
    )
    (net (code "68") (name "unconnected-(J16-PadA25)") (class "Default")
      (node (ref "J16") (pin "A25") (pinfunction "A25_A25") (pintype "passive"))
    )
    (net (code "69") (name "unconnected-(J16-PadA26)") (class "Default")
      (node (ref "J16") (pin "A26") (pinfunction "A26_A26") (pintype "passive"))
    )
    (net (code "70") (name "unconnected-(J16-PadA27)") (class "Default")
      (node (ref "J16") (pin "A27") (pinfunction "A27_A27") (pintype "passive"))
    )
    (net (code "71") (name "unconnected-(J16-PadA28)") (class "Default")
      (node (ref "J16") (pin "A28") (pinfunction "A28_A28") (pintype "passive"))
    )
    (net (code "72") (name "unconnected-(J16-PadA29)") (class "Default")
      (node (ref "J16") (pin "A29") (pinfunction "A29_A29") (pintype "passive"))
    )
    (net (code "73") (name "unconnected-(J16-PadA30)") (class "Default")
      (node (ref "J16") (pin "A30") (pinfunction "A30_A30") (pintype "passive"))
    )
    (net (code "74") (name "unconnected-(J16-PadB6)") (class "Default")
      (node (ref "J16") (pin "B6") (pinfunction "B6_B6") (pintype "passive"))
    )
    (net (code "75") (name "unconnected-(J16-PadB7)") (class "Default")
      (node (ref "J16") (pin "B7") (pinfunction "B7_B7") (pintype "passive"))
    )
    (net (code "76") (name "unconnected-(J16-PadC6)") (class "Default")
      (node (ref "J16") (pin "C6") (pinfunction "C6_C6") (pintype "passive"))
    )
    (net (code "77") (name "unconnected-(J16-PadC7)") (class "Default")
      (node (ref "J16") (pin "C7") (pinfunction "C7_C7") (pintype "passive"))
    )
    (net (code "78") (name "unconnected-(J17-PadA4)") (class "Default")
      (node (ref "J17") (pin "A4") (pinfunction "A4_A4") (pintype "passive"))
    )
    (net (code "79") (name "unconnected-(J17-PadA5)") (class "Default")
      (node (ref "J17") (pin "A5") (pinfunction "A5_A5") (pintype "passive"))
    )
    (net (code "80") (name "unconnected-(J17-PadA6)") (class "Default")
      (node (ref "J17") (pin "A6") (pinfunction "A6_A6") (pintype "passive"))
    )
    (net (code "81") (name "unconnected-(J17-PadA7)") (class "Default")
      (node (ref "J17") (pin "A7") (pinfunction "A7_A7") (pintype "passive"))
    )
    (net (code "82") (name "unconnected-(J17-PadA8)") (class "Default")
      (node (ref "J17") (pin "A8") (pinfunction "A8_A8") (pintype "passive"))
    )
    (net (code "83") (name "unconnected-(J17-PadA9)") (class "Default")
      (node (ref "J17") (pin "A9") (pinfunction "A9_A9") (pintype "passive"))
    )
    (net (code "84") (name "unconnected-(J17-PadA10)") (class "Default")
      (node (ref "J17") (pin "A10") (pinfunction "A10_A10") (pintype "passive"))
    )
    (net (code "85") (name "unconnected-(J17-PadA11)") (class "Default")
      (node (ref "J17") (pin "A11") (pinfunction "A11_A11") (pintype "passive"))
    )
    (net (code "86") (name "unconnected-(J17-PadA12)") (class "Default")
      (node (ref "J17") (pin "A12") (pinfunction "A12_A12") (pintype "passive"))
    )
    (net (code "87") (name "unconnected-(J17-PadA13)") (class "Default")
      (node (ref "J17") (pin "A13") (pinfunction "A13_A13") (pintype "passive"))
    )
    (net (code "88") (name "unconnected-(J17-PadA14)") (class "Default")
      (node (ref "J17") (pin "A14") (pinfunction "A14_A14") (pintype "passive"))
    )
    (net (code "89") (name "unconnected-(J17-PadA15)") (class "Default")
      (node (ref "J17") (pin "A15") (pinfunction "A15_A15") (pintype "passive"))
    )
    (net (code "90") (name "unconnected-(J17-PadA16)") (class "Default")
      (node (ref "J17") (pin "A16") (pinfunction "A16_A16") (pintype "passive"))
    )
    (net (code "91") (name "unconnected-(J17-PadA17)") (class "Default")
      (node (ref "J17") (pin "A17") (pinfunction "A17_A17") (pintype "passive"))
    )
    (net (code "92") (name "unconnected-(J17-PadA18)") (class "Default")
      (node (ref "J17") (pin "A18") (pinfunction "A18_A18") (pintype "passive"))
    )
    (net (code "93") (name "unconnected-(J17-PadA19)") (class "Default")
      (node (ref "J17") (pin "A19") (pinfunction "A19_A19") (pintype "passive"))
    )
    (net (code "94") (name "unconnected-(J17-PadA20)") (class "Default")
      (node (ref "J17") (pin "A20") (pinfunction "A20_A20") (pintype "passive"))
    )
    (net (code "95") (name "unconnected-(J17-PadA21)") (class "Default")
      (node (ref "J17") (pin "A21") (pinfunction "A21_A21") (pintype "passive"))
    )
    (net (code "96") (name "unconnected-(J17-PadA22)") (class "Default")
      (node (ref "J17") (pin "A22") (pinfunction "A22_A22") (pintype "passive"))
    )
    (net (code "97") (name "unconnected-(J17-PadA23)") (class "Default")
      (node (ref "J17") (pin "A23") (pinfunction "A23_A23") (pintype "passive"))
    )
    (net (code "98") (name "unconnected-(J17-PadA24)") (class "Default")
      (node (ref "J17") (pin "A24") (pinfunction "A24_A24") (pintype "passive"))
    )
    (net (code "99") (name "unconnected-(J17-PadA25)") (class "Default")
      (node (ref "J17") (pin "A25") (pinfunction "A25_A25") (pintype "passive"))
    )
    (net (code "100") (name "unconnected-(J17-PadA26)") (class "Default")
      (node (ref "J17") (pin "A26") (pinfunction "A26_A26") (pintype "passive"))
    )
    (net (code "101") (name "unconnected-(J17-PadA27)") (class "Default")
      (node (ref "J17") (pin "A27") (pinfunction "A27_A27") (pintype "passive"))
    )
    (net (code "102") (name "unconnected-(J17-PadA28)") (class "Default")
      (node (ref "J17") (pin "A28") (pinfunction "A28_A28") (pintype "passive"))
    )
    (net (code "103") (name "unconnected-(J17-PadA29)") (class "Default")
      (node (ref "J17") (pin "A29") (pinfunction "A29_A29") (pintype "passive"))
    )
    (net (code "104") (name "unconnected-(J17-PadA30)") (class "Default")
      (node (ref "J17") (pin "A30") (pinfunction "A30_A30") (pintype "passive"))
    )
    (net (code "105") (name "unconnected-(J17-PadA31)") (class "Default")
      (node (ref "J17") (pin "A31") (pinfunction "A31_A31") (pintype "passive"))
    )
    (net (code "106") (name "unconnected-(J17-PadA32)") (class "Default")
      (node (ref "J17") (pin "A32") (pinfunction "A32_A32") (pintype "passive"))
    )
    (net (code "107") (name "unconnected-(J17-PadB4)") (class "Default")
      (node (ref "J17") (pin "B4") (pinfunction "B4_B4") (pintype "passive"))
    )
    (net (code "108") (name "unconnected-(J17-PadB5)") (class "Default")
      (node (ref "J17") (pin "B5") (pinfunction "B5_B5") (pintype "passive"))
    )
    (net (code "109") (name "unconnected-(J17-PadB6)") (class "Default")
      (node (ref "J17") (pin "B6") (pinfunction "B6_B6") (pintype "passive"))
    )
    (net (code "110") (name "unconnected-(J17-PadB7)") (class "Default")
      (node (ref "J17") (pin "B7") (pinfunction "B7_B7") (pintype "passive"))
    )
    (net (code "111") (name "unconnected-(J17-PadB8)") (class "Default")
      (node (ref "J17") (pin "B8") (pinfunction "B8_B8") (pintype "passive"))
    )
    (net (code "112") (name "unconnected-(J17-PadB9)") (class "Default")
      (node (ref "J17") (pin "B9") (pinfunction "B9_B9") (pintype "passive"))
    )
    (net (code "113") (name "unconnected-(J17-PadB10)") (class "Default")
      (node (ref "J17") (pin "B10") (pinfunction "B10_B10") (pintype "passive"))
    )
    (net (code "114") (name "unconnected-(J17-PadB11)") (class "Default")
      (node (ref "J17") (pin "B11") (pinfunction "B11_B11") (pintype "passive"))
    )
    (net (code "115") (name "unconnected-(J17-PadB12)") (class "Default")
      (node (ref "J17") (pin "B12") (pinfunction "B12_B12") (pintype "passive"))
    )
    (net (code "116") (name "unconnected-(J17-PadB13)") (class "Default")
      (node (ref "J17") (pin "B13") (pinfunction "B13_B13") (pintype "passive"))
    )
    (net (code "117") (name "unconnected-(J17-PadB14)") (class "Default")
      (node (ref "J17") (pin "B14") (pinfunction "B14_B14") (pintype "passive"))
    )
    (net (code "118") (name "unconnected-(J17-PadB15)") (class "Default")
      (node (ref "J17") (pin "B15") (pinfunction "B15_B15") (pintype "passive"))
    )
    (net (code "119") (name "unconnected-(J17-PadB16)") (class "Default")
      (node (ref "J17") (pin "B16") (pinfunction "B16_B16") (pintype "passive"))
    )
    (net (code "120") (name "unconnected-(J17-PadB17)") (class "Default")
      (node (ref "J17") (pin "B17") (pinfunction "B17_B17") (pintype "passive"))
    )
    (net (code "121") (name "unconnected-(J17-PadB18)") (class "Default")
      (node (ref "J17") (pin "B18") (pinfunction "B18_B18") (pintype "passive"))
    )
    (net (code "122") (name "unconnected-(J17-PadB19)") (class "Default")
      (node (ref "J17") (pin "B19") (pinfunction "B19_B19") (pintype "passive"))
    )
    (net (code "123") (name "unconnected-(J17-PadB20)") (class "Default")
      (node (ref "J17") (pin "B20") (pinfunction "B20_B20") (pintype "passive"))
    )
    (net (code "124") (name "unconnected-(J17-PadB21)") (class "Default")
      (node (ref "J17") (pin "B21") (pinfunction "B21_B21") (pintype "passive"))
    )
    (net (code "125") (name "unconnected-(J17-PadB22)") (class "Default")
      (node (ref "J17") (pin "B22") (pinfunction "B22_B22") (pintype "passive"))
    )
    (net (code "126") (name "unconnected-(J17-PadB23)") (class "Default")
      (node (ref "J17") (pin "B23") (pinfunction "B23_B23") (pintype "passive"))
    )
    (net (code "127") (name "unconnected-(J17-PadB24)") (class "Default")
      (node (ref "J17") (pin "B24") (pinfunction "B24_B24") (pintype "passive"))
    )
    (net (code "128") (name "unconnected-(J17-PadB25)") (class "Default")
      (node (ref "J17") (pin "B25") (pinfunction "B25_B25") (pintype "passive"))
    )
    (net (code "129") (name "unconnected-(J17-PadB26)") (class "Default")
      (node (ref "J17") (pin "B26") (pinfunction "B26_B26") (pintype "passive"))
    )
    (net (code "130") (name "unconnected-(J17-PadB27)") (class "Default")
      (node (ref "J17") (pin "B27") (pinfunction "B27_B27") (pintype "passive"))
    )
    (net (code "131") (name "unconnected-(J17-PadB28)") (class "Default")
      (node (ref "J17") (pin "B28") (pinfunction "B28_B28") (pintype "passive"))
    )
    (net (code "132") (name "unconnected-(J17-PadB29)") (class "Default")
      (node (ref "J17") (pin "B29") (pinfunction "B29_B29") (pintype "passive"))
    )
    (net (code "133") (name "unconnected-(J17-PadB30)") (class "Default")
      (node (ref "J17") (pin "B30") (pinfunction "B30_B30") (pintype "passive"))
    )
    (net (code "134") (name "unconnected-(J17-PadB31)") (class "Default")
      (node (ref "J17") (pin "B31") (pinfunction "B31_B31") (pintype "passive"))
    )
    (net (code "135") (name "unconnected-(J17-PadB32)") (class "Default")
      (node (ref "J17") (pin "B32") (pinfunction "B32_B32") (pintype "passive"))
    )
    (net (code "136") (name "unconnected-(J17-PadC4)") (class "Default")
      (node (ref "J17") (pin "C4") (pinfunction "C4_C4") (pintype "passive"))
    )
    (net (code "137") (name "unconnected-(J17-PadC5)") (class "Default")
      (node (ref "J17") (pin "C5") (pinfunction "C5_C5") (pintype "passive"))
    )
    (net (code "138") (name "unconnected-(J17-PadC6)") (class "Default")
      (node (ref "J17") (pin "C6") (pinfunction "C6_C6") (pintype "passive"))
    )
    (net (code "139") (name "unconnected-(J17-PadC7)") (class "Default")
      (node (ref "J17") (pin "C7") (pinfunction "C7_C7") (pintype "passive"))
    )
    (net (code "140") (name "unconnected-(J17-PadC8)") (class "Default")
      (node (ref "J17") (pin "C8") (pinfunction "C8_C8") (pintype "passive"))
    )
    (net (code "141") (name "unconnected-(J17-PadC9)") (class "Default")
      (node (ref "J17") (pin "C9") (pinfunction "C9_C9") (pintype "passive"))
    )
    (net (code "142") (name "unconnected-(J17-PadC10)") (class "Default")
      (node (ref "J17") (pin "C10") (pinfunction "C10_C10") (pintype "passive"))
    )
    (net (code "143") (name "unconnected-(J17-PadC11)") (class "Default")
      (node (ref "J17") (pin "C11") (pinfunction "C11_C11") (pintype "passive"))
    )
    (net (code "144") (name "unconnected-(J17-PadC12)") (class "Default")
      (node (ref "J17") (pin "C12") (pinfunction "C12_C12") (pintype "passive"))
    )
    (net (code "145") (name "unconnected-(J17-PadC13)") (class "Default")
      (node (ref "J17") (pin "C13") (pinfunction "C13_C13") (pintype "passive"))
    )
    (net (code "146") (name "unconnected-(J17-PadC14)") (class "Default")
      (node (ref "J17") (pin "C14") (pinfunction "C14_C14") (pintype "passive"))
    )
    (net (code "147") (name "unconnected-(J17-PadC15)") (class "Default")
      (node (ref "J17") (pin "C15") (pinfunction "C15_C15") (pintype "passive"))
    )
    (net (code "148") (name "unconnected-(J17-PadC16)") (class "Default")
      (node (ref "J17") (pin "C16") (pinfunction "C16_C16") (pintype "passive"))
    )
    (net (code "149") (name "unconnected-(J17-PadC17)") (class "Default")
      (node (ref "J17") (pin "C17") (pinfunction "C17_C17") (pintype "passive"))
    )
    (net (code "150") (name "unconnected-(J17-PadC18)") (class "Default")
      (node (ref "J17") (pin "C18") (pinfunction "C18_C18") (pintype "passive"))
    )
    (net (code "151") (name "unconnected-(J17-PadC19)") (class "Default")
      (node (ref "J17") (pin "C19") (pinfunction "C19_C19") (pintype "passive"))
    )
    (net (code "152") (name "unconnected-(J17-PadC20)") (class "Default")
      (node (ref "J17") (pin "C20") (pinfunction "C20_C20") (pintype "passive"))
    )
    (net (code "153") (name "unconnected-(J17-PadC21)") (class "Default")
      (node (ref "J17") (pin "C21") (pinfunction "C21_C21") (pintype "passive"))
    )
    (net (code "154") (name "unconnected-(J17-PadC22)") (class "Default")
      (node (ref "J17") (pin "C22") (pinfunction "C22_C22") (pintype "passive"))
    )
    (net (code "155") (name "unconnected-(J17-PadC23)") (class "Default")
      (node (ref "J17") (pin "C23") (pinfunction "C23_C23") (pintype "passive"))
    )
    (net (code "156") (name "unconnected-(J17-PadC24)") (class "Default")
      (node (ref "J17") (pin "C24") (pinfunction "C24_C24") (pintype "passive"))
    )
    (net (code "157") (name "unconnected-(J17-PadC25)") (class "Default")
      (node (ref "J17") (pin "C25") (pinfunction "C25_C25") (pintype "passive"))
    )
    (net (code "158") (name "unconnected-(J17-PadC26)") (class "Default")
      (node (ref "J17") (pin "C26") (pinfunction "C26_C26") (pintype "passive"))
    )
    (net (code "159") (name "unconnected-(J17-PadC27)") (class "Default")
      (node (ref "J17") (pin "C27") (pinfunction "C27_C27") (pintype "passive"))
    )
    (net (code "160") (name "unconnected-(J17-PadC28)") (class "Default")
      (node (ref "J17") (pin "C28") (pinfunction "C28_C28") (pintype "passive"))
    )
    (net (code "161") (name "unconnected-(J17-PadC29)") (class "Default")
      (node (ref "J17") (pin "C29") (pinfunction "C29_C29") (pintype "passive"))
    )
    (net (code "162") (name "unconnected-(J17-PadC30)") (class "Default")
      (node (ref "J17") (pin "C30") (pinfunction "C30_C30") (pintype "passive"))
    )
    (net (code "163") (name "unconnected-(J17-PadC31)") (class "Default")
      (node (ref "J17") (pin "C31") (pinfunction "C31_C31") (pintype "passive"))
    )
    (net (code "164") (name "unconnected-(J17-PadC32)") (class "Default")
      (node (ref "J17") (pin "C32") (pinfunction "C32_C32") (pintype "passive"))
    )
    (net (code "165") (name "unconnected-(RN1-Pad5)") (class "Default")
      (node (ref "RN1") (pin "5") (pinfunction "5_5") (pintype "passive"))
    )
    (net (code "166") (name "unconnected-(US3A-Q-Pad4)") (class "Default")
      (node (ref "US3") (pin "4") (pinfunction "Q_4") (pintype "passive"))
    )
  )
)
